# IOa.net
KiCad netlist of a schematic drawn in Altium Designer
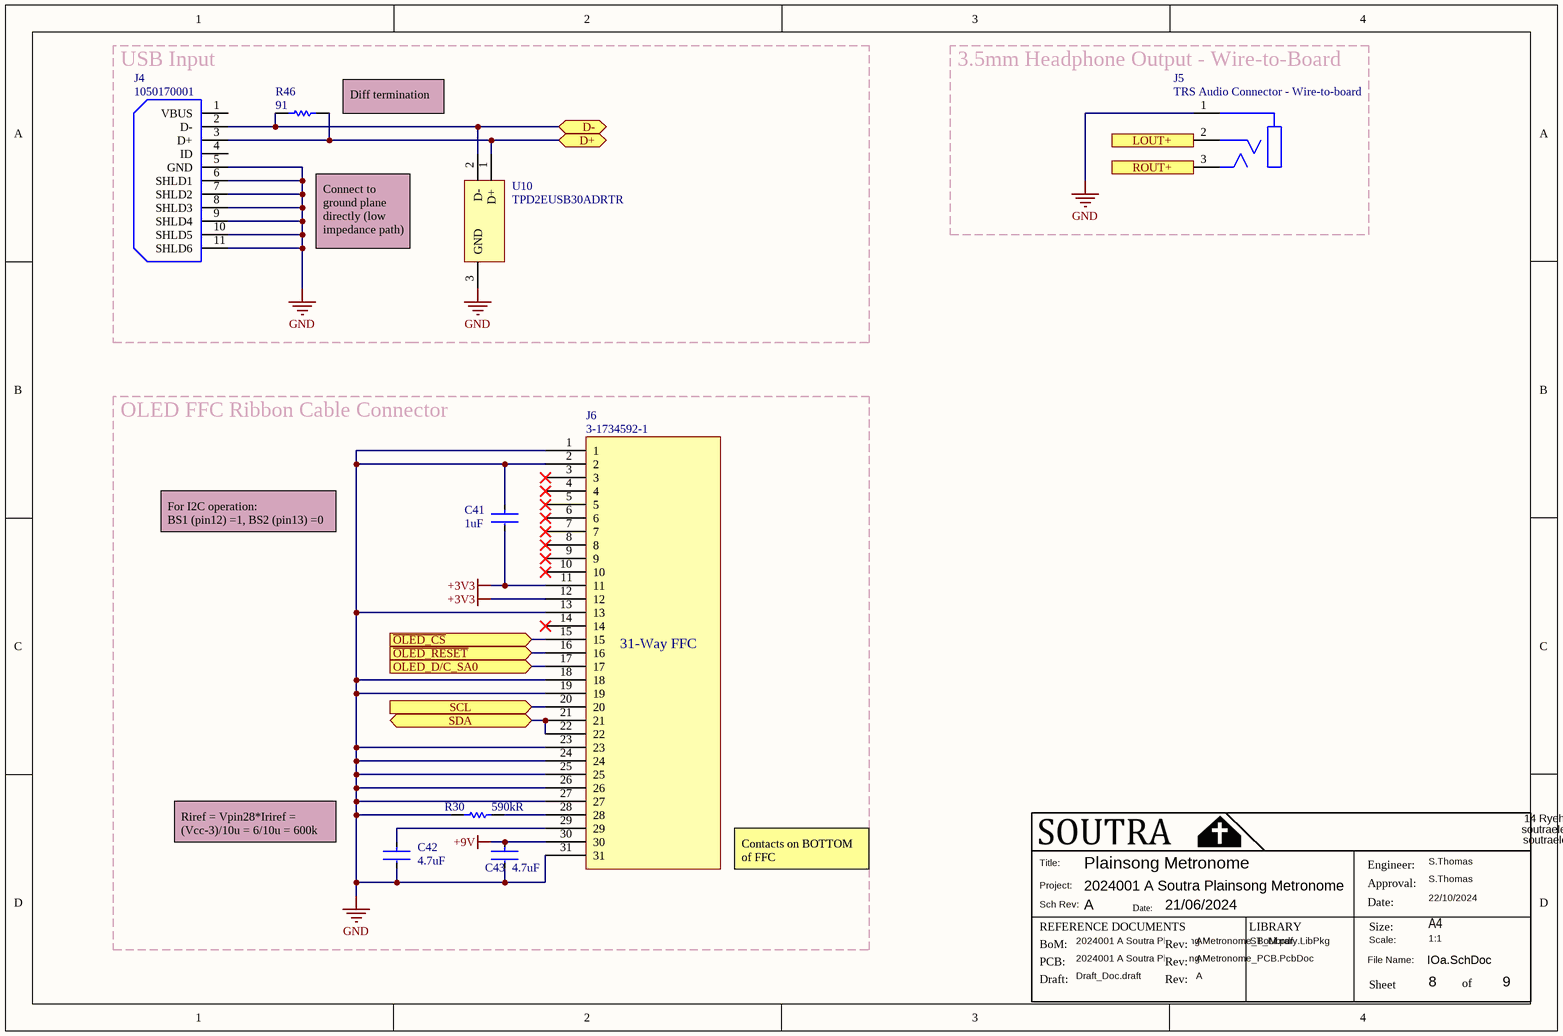
[diagram p0: IOa.SchDoc]

(export (version "E")
  (design (tool "Eeschema 10.0.6"))
  (components
    (comp (ref "C41")
      (value "1uF")
      (footprint "CAPC1005X06L")
      (fields
        (field (name "MANUFACTURER") "Yageo")
        (field (name "MANUFACTURER PART NUMBER") "CC0402KRX5R6BB105")
        (field (name "ALTERNATIVE PART") "0402ZD105KAT2A")
      )
      (libsource (lib "ST_Library") (part "CC0402KRX5R6BB105"))
    )
    (comp (ref "C42")
      (value "4.7uF")
      (footprint "CC1206-IPC_A")
      (fields
        (field (name "MANUFACTURER") "Samsung")
        (field (name "MANUFACTURER PART NUMBER") "CL31B475KAHNNNE")
      )
      (libsource (lib "ST_Library") (part "CL31B475KAHNNNE"))
    )
    (comp (ref "C43")
      (value "4.7uF")
      (footprint "CC1206-IPC_A")
      (fields
        (field (name "MANUFACTURER") "Samsung")
        (field (name "MANUFACTURER PART NUMBER") "CL31B475KAHNNNE")
      )
      (libsource (lib "ST_Library") (part "CL31B475KAHNNNE"))
    )
    (comp (ref "J4")
      (value "1050170001")
      (footprint "1050170001_USB-MICRO-B_V")
      (fields (field (name "MANUFACTURER PART NUMBER") "105017-0001") (field (name "MANUFACTURER") "Molex"))
      (libsource (lib "ST_Library") (part "1050170001"))
    )
    (comp (ref "J5")
      (value "TRS Audio Connector - Wire-to-board")
      (footprint "J_GENERIC_PIN-HEADER_2.54_1X3")
      (libsource (lib "ST_Library") (part "J_AUDIO_TRS"))
    )
    (comp (ref "J6")
      (value "3-1734592-1")
      (footprint "AMP-TE_3-1734592-1")
      (fields (field (name "MANUFACTURER") "TE Connectivity"))
      (libsource (lib "ST_Library") (part "3-1734592-1"))
    )
    (comp (ref "R30")
      (value "590kR")
      (footprint "RESC_0402_1005X40X25LL05T10")
      (fields
        (field (name "MANUFACTURER") "Yageo")
        (field (name "MANUFACTURER PART NUMBER") "RC0402FR-07590KL")
        (field (name "TOLERANCE") "1%")
      )
      (libsource (lib "ST_Library") (part "RC0402FR-07590KL"))
    )
    (comp (ref "R46")
      (value "91")
      (footprint "RESC_0603_1608X06L")
      (description "Res Thick Film 0603 91 Ohm 1% 0.25W(1/4W) ±100ppm/C Pad SMD Automotive T/R")
      (fields
        (field (name "MANUFACTURER") "Panasonic")
        (field (name "MANUFACTURER PART NUMBER") "ERJ-PA3F91R0V")
      )
      (libsource (lib "ST_Library") (part "ERJ-PA3F91R0V"))
    )
    (comp (ref "U10")
      (value "TPD2EUSB30ADRTR")
      (footprint "DRT0003A")
      (fields (field (name "MANUFACTURER") "Texas Instruments"))
      (libsource (lib "ST_Library") (part "TPD2EUSB30ADRTR"))
    )
  )
  (nets
    (net (code "1") (name "+3V3") (class "Default")
      (node (ref "C41") (pin "2") (pinfunction "2_2") (pintype "passive"))
      (node (ref "J6") (pin "11") (pinfunction "11_11") (pintype "passive"))
      (node (ref "J6") (pin "12") (pinfunction "12_12") (pintype "passive"))
    )
    (net (code "2") (name "+9V") (class "Default")
      (node (ref "C43") (pin "1") (pinfunction "1_1") (pintype "passive"))
      (node (ref "J6") (pin "30") (pinfunction "30_30") (pintype "passive"))
    )
    (net (code "3") (name "/D+") (class "Default")
      (node (ref "J4") (pin "3") (pinfunction "D+_3") (pintype "passive"))
      (node (ref "R46") (pin "2") (pinfunction "2_2") (pintype "passive"))
      (node (ref "U10") (pin "1") (pinfunction "D+_1") (pintype "passive"))
    )
    (net (code "4") (name "/D-") (class "Default")
      (node (ref "J4") (pin "2") (pinfunction "D-_2") (pintype "passive"))
      (node (ref "R46") (pin "1") (pinfunction "1_1") (pintype "passive"))
      (node (ref "U10") (pin "2") (pinfunction "D-_2") (pintype "passive"))
    )
    (net (code "5") (name "/LOUT+") (class "Default")
      (node (ref "J5") (pin "2") (pinfunction "2_2") (pintype "passive"))
    )
    (net (code "6") (name "/OLED_D{slash}C_SA0") (class "Default")
      (node (ref "J6") (pin "17") (pinfunction "17_17") (pintype "passive"))
    )
    (net (code "7") (name "/ROUT+") (class "Default")
      (node (ref "J5") (pin "3") (pinfunction "3_3") (pintype "passive"))
    )
    (net (code "8") (name "/SCL") (class "Default")
      (node (ref "J6") (pin "20") (pinfunction "20_20") (pintype "passive"))
    )
    (net (code "9") (name "/SDA") (class "Default")
      (node (ref "J6") (pin "21") (pinfunction "21_21") (pintype "passive"))
      (node (ref "J6") (pin "22") (pinfunction "22_22") (pintype "passive"))
    )
    (net (code "10") (name "/~{OLED_CS}") (class "Default")
      (node (ref "J6") (pin "15") (pinfunction "15_15") (pintype "passive"))
    )
    (net (code "11") (name "/~{OLED_RESET}") (class "Default")
      (node (ref "J6") (pin "16") (pinfunction "16_16") (pintype "passive"))
    )
    (net (code "12") (name "GND") (class "Default")
      (node (ref "C41") (pin "1") (pinfunction "1_1") (pintype "passive"))
      (node (ref "C42") (pin "2") (pinfunction "2_2") (pintype "passive"))
      (node (ref "C43") (pin "2") (pinfunction "2_2") (pintype "passive"))
      (node (ref "J4") (pin "10") (pinfunction "SHLD5_10") (pintype "passive"))
      (node (ref "J4") (pin "11") (pinfunction "SHLD6_11") (pintype "passive"))
      (node (ref "J4") (pin "5") (pinfunction "GND_5") (pintype "passive"))
      (node (ref "J4") (pin "6") (pinfunction "SHLD1_6") (pintype "passive"))
      (node (ref "J4") (pin "7") (pinfunction "SHLD2_7") (pintype "passive"))
      (node (ref "J4") (pin "8") (pinfunction "SHLD3_8") (pintype "passive"))
      (node (ref "J4") (pin "9") (pinfunction "SHLD4_9") (pintype "passive"))
      (node (ref "J5") (pin "1") (pinfunction "1_1") (pintype "passive"))
      (node (ref "J6") (pin "1") (pinfunction "1_1") (pintype "passive"))
      (node (ref "J6") (pin "13") (pinfunction "13_13") (pintype "passive"))
      (node (ref "J6") (pin "18") (pinfunction "18_18") (pintype "passive"))
      (node (ref "J6") (pin "19") (pinfunction "19_19") (pintype "passive"))
      (node (ref "J6") (pin "2") (pinfunction "2_2") (pintype "passive"))
      (node (ref "J6") (pin "23") (pinfunction "23_23") (pintype "passive"))
      (node (ref "J6") (pin "24") (pinfunction "24_24") (pintype "passive"))
      (node (ref "J6") (pin "25") (pinfunction "25_25") (pintype "passive"))
      (node (ref "J6") (pin "26") (pinfunction "26_26") (pintype "passive"))
      (node (ref "J6") (pin "27") (pinfunction "27_27") (pintype "passive"))
      (node (ref "J6") (pin "31") (pinfunction "31_31") (pintype "passive"))
      (node (ref "R30") (pin "1") (pinfunction "1_1") (pintype "passive"))
      (node (ref "U10") (pin "3") (pinfunction "GND_3") (pintype "power_in"))
    )
    (net (code "13") (name "Net-(C42-Pad1)") (class "Default")
      (node (ref "C42") (pin "1") (pinfunction "1_1") (pintype "passive"))
      (node (ref "J6") (pin "29") (pinfunction "29_29") (pintype "passive"))
    )
    (net (code "14") (name "Net-(J6-Pad28)") (class "Default")
      (node (ref "J6") (pin "28") (pinfunction "28_28") (pintype "passive"))
      (node (ref "R30") (pin "2") (pinfunction "2_2") (pintype "passive"))
    )
    (net (code "15") (name "unconnected-(J4-ID-Pad4)") (class "Default")
      (node (ref "J4") (pin "4") (pinfunction "ID_4") (pintype "passive"))
    )
    (net (code "16") (name "unconnected-(J4-VBUS-Pad1)") (class "Default")
      (node (ref "J4") (pin "1") (pinfunction "VBUS_1") (pintype "passive"))
    )
    (net (code "17") (name "unconnected-(J6-Pad3)") (class "Default")
      (node (ref "J6") (pin "3") (pinfunction "3_3") (pintype "passive+no_connect"))
    )
    (net (code "18") (name "unconnected-(J6-Pad4)") (class "Default")
      (node (ref "J6") (pin "4") (pinfunction "4_4") (pintype "passive+no_connect"))
    )
    (net (code "19") (name "unconnected-(J6-Pad5)") (class "Default")
      (node (ref "J6") (pin "5") (pinfunction "5_5") (pintype "passive+no_connect"))
    )
    (net (code "20") (name "unconnected-(J6-Pad6)") (class "Default")
      (node (ref "J6") (pin "6") (pinfunction "6_6") (pintype "passive+no_connect"))
    )
    (net (code "21") (name "unconnected-(J6-Pad7)") (class "Default")
      (node (ref "J6") (pin "7") (pinfunction "7_7") (pintype "passive+no_connect"))
    )
    (net (code "22") (name "unconnected-(J6-Pad8)") (class "Default")
      (node (ref "J6") (pin "8") (pinfunction "8_8") (pintype "passive+no_connect"))
    )
    (net (code "23") (name "unconnected-(J6-Pad9)") (class "Default")
      (node (ref "J6") (pin "9") (pinfunction "9_9") (pintype "passive+no_connect"))
    )
    (net (code "24") (name "unconnected-(J6-Pad10)") (class "Default")
      (node (ref "J6") (pin "10") (pinfunction "10_10") (pintype "passive+no_connect"))
    )
    (net (code "25") (name "unconnected-(J6-Pad14)") (class "Default")
      (node (ref "J6") (pin "14") (pinfunction "14_14") (pintype "passive+no_connect"))
    )
  )
)
